# Keyboard_Connector.net
KiCad netlist of a schematic drawn in EAGLE
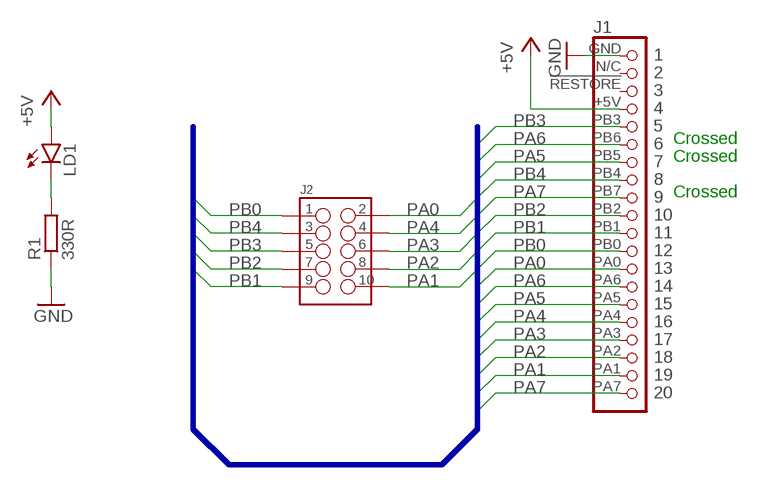
[diagram p0: schematic, sheet 1]

(export (version "E")
  (design (tool "Eeschema 10.0.6"))
  (components
    (comp (ref "J1")
      (value "C64_KEYBOARD_CONNECTOR")
      (footprint "eagle-import:C64_KEYBOARD_CONNECTOR")
      (libsource (lib "eagle-import") (part "C64_KEYBOARD_CONNECTOR"))
    )
    (comp (ref "J2")
      (value "HEADER_2X5-WALLED")
      (footprint "eagle-import:2X5_HEADER_WALLED")
      (libsource (lib "eagle-import") (part "HEADER_2X5-WALLED"))
    )
    (comp (ref "LD1")
      (value "LED1206")
      (footprint "eagle-import:LED-1206")
      (libsource (lib "eagle-import") (part "LED1206"))
    )
    (comp (ref "R1")
      (value "330R")
      (footprint "eagle-import:R0805")
      (libsource (lib "eagle-import") (part "R-EU_R0805"))
    )
  )
  (nets
    (net (code "1") (name "+5V") (class "Default")
      (node (ref "J1") (pin "+5V") (pinfunction "+5V_+5V") (pintype "power_in"))
      (node (ref "LD1") (pin "A") (pinfunction "A_A") (pintype "passive"))
    )
    (net (code "2") (name "/PA0") (class "Default")
      (node (ref "J1") (pin "PA0") (pinfunction "PA0_PA0") (pintype "passive"))
      (node (ref "J2") (pin "2") (pinfunction "2_2") (pintype "bidirectional"))
    )
    (net (code "3") (name "/PA1") (class "Default")
      (node (ref "J1") (pin "PA1") (pinfunction "PA1_PA1") (pintype "passive"))
      (node (ref "J2") (pin "10") (pinfunction "10_10") (pintype "bidirectional"))
    )
    (net (code "4") (name "/PA2") (class "Default")
      (node (ref "J1") (pin "PA2") (pinfunction "PA2_PA2") (pintype "passive"))
      (node (ref "J2") (pin "8") (pinfunction "8_8") (pintype "bidirectional"))
    )
    (net (code "5") (name "/PA3") (class "Default")
      (node (ref "J1") (pin "PA3") (pinfunction "PA3_PA3") (pintype "passive"))
      (node (ref "J2") (pin "6") (pinfunction "6_6") (pintype "bidirectional"))
    )
    (net (code "6") (name "/PA4") (class "Default")
      (node (ref "J1") (pin "PA4") (pinfunction "PA4_PA4") (pintype "passive"))
      (node (ref "J2") (pin "4") (pinfunction "4_4") (pintype "bidirectional"))
    )
    (net (code "7") (name "/PA5") (class "Default")
      (node (ref "J1") (pin "PA5") (pinfunction "PA5_PA5") (pintype "passive"))
      (node (ref "J1") (pin "PB5") (pinfunction "PB5_PB5") (pintype "passive"))
    )
    (net (code "8") (name "/PA6") (class "Default")
      (node (ref "J1") (pin "PA6") (pinfunction "PA6_PA6") (pintype "passive"))
      (node (ref "J1") (pin "PB6") (pinfunction "PB6_PB6") (pintype "passive"))
    )
    (net (code "9") (name "/PA7") (class "Default")
      (node (ref "J1") (pin "PA7") (pinfunction "PA7_PA7") (pintype "passive"))
      (node (ref "J1") (pin "PB7") (pinfunction "PB7_PB7") (pintype "passive"))
    )
    (net (code "10") (name "/PB0") (class "Default")
      (node (ref "J1") (pin "PB0") (pinfunction "PB0_PB0") (pintype "passive"))
      (node (ref "J2") (pin "1") (pinfunction "1_1") (pintype "bidirectional"))
    )
    (net (code "11") (name "/PB1") (class "Default")
      (node (ref "J1") (pin "PB1") (pinfunction "PB1_PB1") (pintype "passive"))
      (node (ref "J2") (pin "9") (pinfunction "9_9") (pintype "bidirectional"))
    )
    (net (code "12") (name "/PB2") (class "Default")
      (node (ref "J1") (pin "PB2") (pinfunction "PB2_PB2") (pintype "passive"))
      (node (ref "J2") (pin "7") (pinfunction "7_7") (pintype "bidirectional"))
    )
    (net (code "13") (name "/PB3") (class "Default")
      (node (ref "J1") (pin "PB3") (pinfunction "PB3_PB3") (pintype "passive"))
      (node (ref "J2") (pin "5") (pinfunction "5_5") (pintype "bidirectional"))
    )
    (net (code "14") (name "/PB4") (class "Default")
      (node (ref "J1") (pin "PB4") (pinfunction "PB4_PB4") (pintype "passive"))
      (node (ref "J2") (pin "3") (pinfunction "3_3") (pintype "bidirectional"))
    )
    (net (code "15") (name "GND") (class "Default")
      (node (ref "J1") (pin "GND") (pinfunction "GND_GND") (pintype "power_in"))
      (node (ref "R1") (pin "1") (pinfunction "1_1") (pintype "passive"))
    )
    (net (code "16") (name "Net-(LD1-PadC)") (class "Default")
      (node (ref "LD1") (pin "C") (pinfunction "C_C") (pintype "passive"))
      (node (ref "R1") (pin "2") (pinfunction "2_2") (pintype "passive"))
    )
    (net (code "17") (name "unconnected-(J1-PadN{slash}C)") (class "Default")
      (node (ref "J1") (pin "N/C") (pinfunction "N/C_N/C") (pintype "no_connect"))
    )
    (net (code "18") (name "unconnected-(J1-~{RESTORE}-Pad!RESTORE)") (class "Default")
      (node (ref "J1") (pin "!RESTORE") (pinfunction "~{RESTORE}_!RESTORE") (pintype "passive"))
    )
  )
)
